# POE_V1.net
KiCad netlist of a schematic drawn in EAGLE
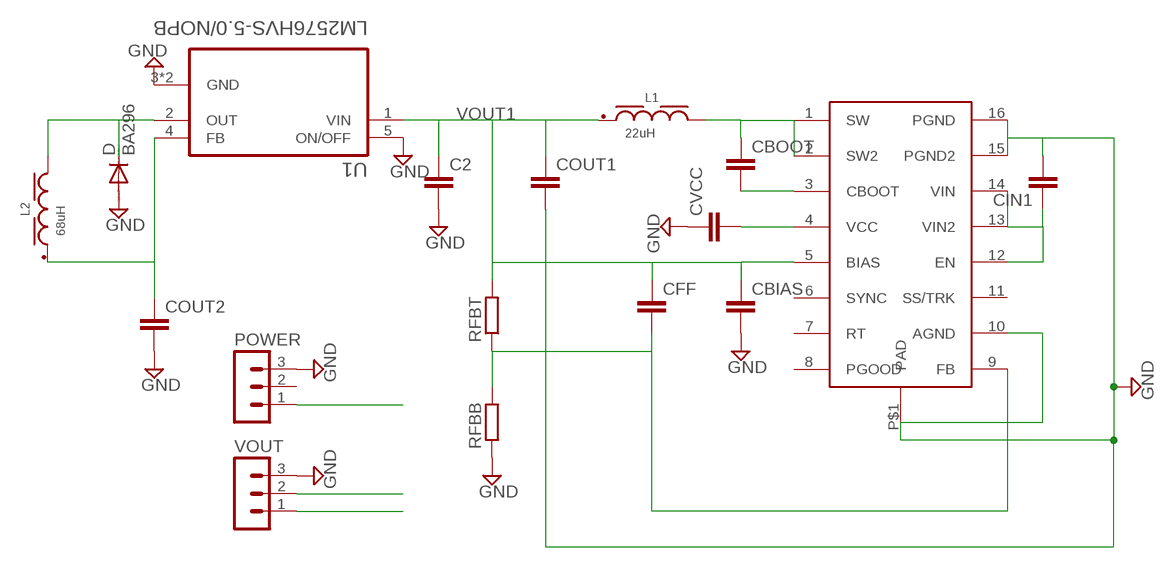
[diagram p0: schematic, sheet 1]

(export (version "E")
  (design (tool "Eeschema 10.0.6"))
  (components
    (comp (ref "C2")
      (value "C-EUC1206")
      (footprint "eagle-import:C1206")
      (libsource (lib "eagle-import") (part "C-EUC1206"))
    )
    (comp (ref "CBIAS")
      (value "C-EUC1206")
      (footprint "eagle-import:C1206")
      (libsource (lib "eagle-import") (part "C-EUC1206"))
    )
    (comp (ref "CBOOT")
      (value "C-EUC1206")
      (footprint "eagle-import:C1206")
      (libsource (lib "eagle-import") (part "C-EUC1206"))
    )
    (comp (ref "CFF")
      (value "C-EUC1206")
      (footprint "eagle-import:C1206")
      (libsource (lib "eagle-import") (part "C-EUC1206"))
    )
    (comp (ref "CIN1")
      (value "C-EUC1206")
      (footprint "eagle-import:C1206")
      (libsource (lib "eagle-import") (part "C-EUC1206"))
    )
    (comp (ref "COUT1")
      (value "C-EUC1206")
      (footprint "eagle-import:C1206")
      (libsource (lib "eagle-import") (part "C-EUC1206"))
    )
    (comp (ref "COUT2")
      (value "C-EUC1206")
      (footprint "eagle-import:C1206")
      (libsource (lib "eagle-import") (part "C-EUC1206"))
    )
    (comp (ref "CVCC")
      (value "C-EUC1206")
      (footprint "eagle-import:C1206")
      (libsource (lib "eagle-import") (part "C-EUC1206"))
    )
    (comp (ref "D")
      (value "BA296")
      (footprint "eagle-import:P2-15")
      (libsource (lib "eagle-import") (part "BA296"))
    )
    (comp (ref "L1")
      (value "22uH")
      (footprint "eagle-import:WE-PD_1260")
      (libsource (lib "eagle-import") (part "WE-PD_1260_744771122"))
    )
    (comp (ref "L2")
      (value "68uH")
      (footprint "eagle-import:WE-PD_1210")
      (libsource (lib "eagle-import") (part "WE-PD_1210_7447709680"))
    )
    (comp (ref "POWER")
      (value "MA03-1")
      (footprint "eagle-import:MA03-1")
      (libsource (lib "eagle-import") (part "MA03-1"))
    )
    (comp (ref "RFBB")
      (value "R-EU_M1206")
      (footprint "eagle-import:M1206")
      (libsource (lib "eagle-import") (part "R-EU_M1206"))
    )
    (comp (ref "RFBT")
      (value "R-EU_M1206")
      (footprint "eagle-import:M1206")
      (libsource (lib "eagle-import") (part "R-EU_M1206"))
    )
    (comp (ref "U$1")
      (value "LM46002")
      (footprint "eagle-import:TSSOP16")
      (libsource (lib "eagle-import") (part "LM46002"))
    )
    (comp (ref "U1")
      (value "LM2576HVS-5.0/NOPB")
      (footprint "eagle-import:VREG_TPS79625KTTR")
      (fields
        (field (name "DIGI-KEY_PART_NUMBER") "LM2576HVS-5.0/NOPB-ND")
        (field (name "MF") "Texas Instruments")
      )
      (libsource (lib "eagle-import") (part "LM2576HVS-5.0/NOPB"))
    )
    (comp (ref "VOUT")
      (value "MA03-1")
      (footprint "eagle-import:MA03-1")
      (libsource (lib "eagle-import") (part "MA03-1"))
    )
  )
  (nets
    (net (code "1") (name "/VIN") (class "Default")
      (node (ref "CIN1") (pin "1") (pinfunction "1_1") (pintype "passive"))
      (node (ref "POWER") (pin "1") (pinfunction "1_1") (pintype "passive"))
      (node (ref "U$1") (pin "12") (pinfunction "EN_12") (pintype "bidirectional"))
      (node (ref "U$1") (pin "13") (pinfunction "VIN2_13") (pintype "bidirectional"))
      (node (ref "U$1") (pin "14") (pinfunction "VIN_14") (pintype "bidirectional"))
    )
    (net (code "2") (name "/VOUT1") (class "Default")
      (node (ref "C2") (pin "1") (pinfunction "1_1") (pintype "passive"))
      (node (ref "CBIAS") (pin "1") (pinfunction "1_1") (pintype "passive"))
      (node (ref "CFF") (pin "1") (pinfunction "1_1") (pintype "passive"))
      (node (ref "COUT1") (pin "1") (pinfunction "1_1") (pintype "passive"))
      (node (ref "L1") (pin "1") (pinfunction "1_1") (pintype "passive"))
      (node (ref "RFBT") (pin "2") (pinfunction "2_2") (pintype "passive"))
      (node (ref "U$1") (pin "5") (pinfunction "BIAS_5") (pintype "bidirectional"))
      (node (ref "U1") (pin "1") (pinfunction "VIN_1") (pintype "input"))
      (node (ref "VOUT") (pin "1") (pinfunction "1_1") (pintype "passive"))
    )
    (net (code "3") (name "/VOUT2") (class "Default")
      (node (ref "COUT2") (pin "1") (pinfunction "1_1") (pintype "passive"))
      (node (ref "L2") (pin "1") (pinfunction "1_1") (pintype "passive"))
      (node (ref "U1") (pin "4") (pinfunction "FB_4") (pintype "output"))
      (node (ref "VOUT") (pin "2") (pinfunction "2_2") (pintype "passive"))
    )
    (net (code "4") (name "GND") (class "Default")
      (node (ref "C2") (pin "2") (pinfunction "2_2") (pintype "passive"))
      (node (ref "CBIAS") (pin "2") (pinfunction "2_2") (pintype "passive"))
      (node (ref "CIN1") (pin "2") (pinfunction "2_2") (pintype "passive"))
      (node (ref "COUT1") (pin "2") (pinfunction "2_2") (pintype "passive"))
      (node (ref "COUT2") (pin "2") (pinfunction "2_2") (pintype "passive"))
      (node (ref "CVCC") (pin "1") (pinfunction "1_1") (pintype "passive"))
      (node (ref "D") (pin "A") (pinfunction "A_A") (pintype "passive"))
      (node (ref "POWER") (pin "3") (pinfunction "3_3") (pintype "passive"))
      (node (ref "RFBB") (pin "1") (pinfunction "1_1") (pintype "passive"))
      (node (ref "U$1") (pin "10") (pinfunction "AGND_10") (pintype "bidirectional"))
      (node (ref "U$1") (pin "15") (pinfunction "PGND2_15") (pintype "bidirectional"))
      (node (ref "U$1") (pin "16") (pinfunction "PGND_16") (pintype "bidirectional"))
      (node (ref "U$1") (pin "P$1") (pinfunction "PAD_P$1") (pintype "bidirectional"))
      (node (ref "U1") (pin "3") (pinfunction "GND_3") (pintype "power_in"))
      (node (ref "U1") (pin "5") (pinfunction "ON/OFF_5") (pintype "input"))
      (node (ref "U1") (pin "6") (pinfunction "GND_6") (pintype "power_in"))
      (node (ref "VOUT") (pin "3") (pinfunction "3_3") (pintype "passive"))
    )
    (net (code "5") (name "Net-(U$1-CBOOT)") (class "Default")
      (node (ref "CBOOT") (pin "2") (pinfunction "2_2") (pintype "passive"))
      (node (ref "U$1") (pin "3") (pinfunction "CBOOT_3") (pintype "bidirectional"))
    )
    (net (code "6") (name "Net-(U$1-FB)") (class "Default")
      (node (ref "CFF") (pin "2") (pinfunction "2_2") (pintype "passive"))
      (node (ref "RFBB") (pin "2") (pinfunction "2_2") (pintype "passive"))
      (node (ref "RFBT") (pin "1") (pinfunction "1_1") (pintype "passive"))
      (node (ref "U$1") (pin "9") (pinfunction "FB_9") (pintype "bidirectional"))
    )
    (net (code "7") (name "Net-(U$1-SW)") (class "Default")
      (node (ref "CBOOT") (pin "1") (pinfunction "1_1") (pintype "passive"))
      (node (ref "L1") (pin "2") (pinfunction "2_2") (pintype "passive"))
      (node (ref "U$1") (pin "1") (pinfunction "SW_1") (pintype "bidirectional"))
      (node (ref "U$1") (pin "2") (pinfunction "SW2_2") (pintype "bidirectional"))
    )
    (net (code "8") (name "Net-(U$1-VCC)") (class "Default")
      (node (ref "CVCC") (pin "2") (pinfunction "2_2") (pintype "passive"))
      (node (ref "U$1") (pin "4") (pinfunction "VCC_4") (pintype "bidirectional"))
    )
    (net (code "9") (name "Net-(U1-OUT)") (class "Default")
      (node (ref "D") (pin "C") (pinfunction "C_C") (pintype "passive"))
      (node (ref "L2") (pin "2") (pinfunction "2_2") (pintype "passive"))
      (node (ref "U1") (pin "2") (pinfunction "OUT_2") (pintype "output"))
    )
    (net (code "10") (name "unconnected-(POWER-Pad2)") (class "Default")
      (node (ref "POWER") (pin "2") (pinfunction "2_2") (pintype "passive"))
    )
    (net (code "11") (name "unconnected-(U$1-PGOOD-Pad8)") (class "Default")
      (node (ref "U$1") (pin "8") (pinfunction "PGOOD_8") (pintype "bidirectional"))
    )
    (net (code "12") (name "unconnected-(U$1-RT-Pad7)") (class "Default")
      (node (ref "U$1") (pin "7") (pinfunction "RT_7") (pintype "bidirectional"))
    )
    (net (code "13") (name "unconnected-(U$1-SS{slash}TRK-Pad11)") (class "Default")
      (node (ref "U$1") (pin "11") (pinfunction "SS/TRK_11") (pintype "bidirectional"))
    )
    (net (code "14") (name "unconnected-(U$1-SYNC-Pad6)") (class "Default")
      (node (ref "U$1") (pin "6") (pinfunction "SYNC_6") (pintype "bidirectional"))
    )
  )
)
